# VIVA_PIC16_1591A.net
KiCad netlist of a schematic drawn in EAGLE
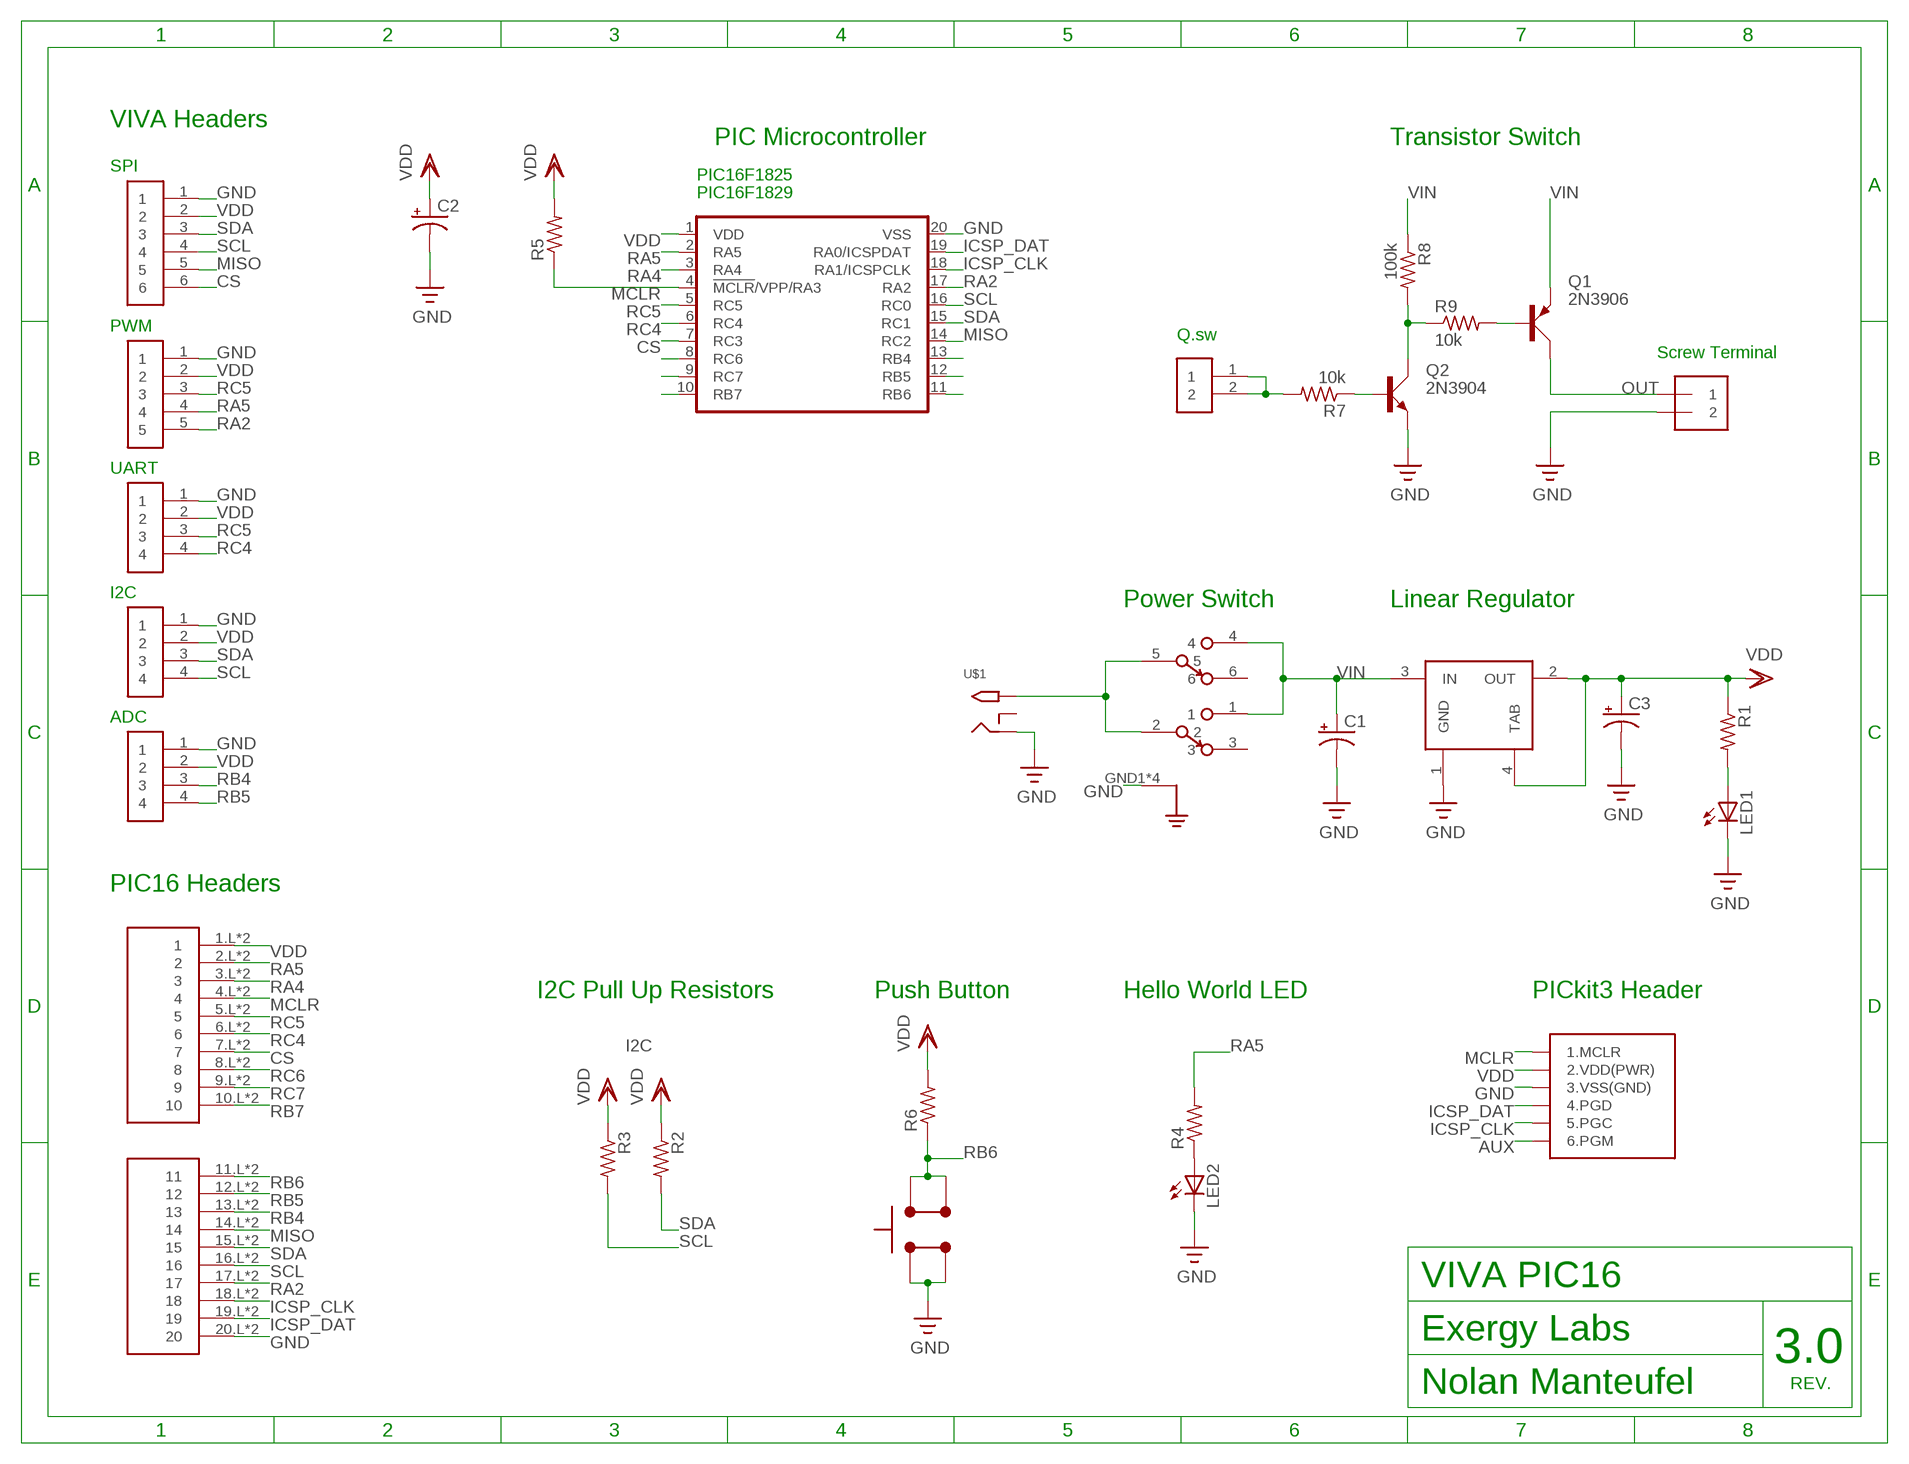
[diagram p0: schematic, sheet 1]

(export (version "E")
  (design (tool "Eeschema 10.0.6"))
  (components
    (comp (ref "C1")
      (value "CPOL-USE2.5-6")
      (footprint "eagle-import:E2,5-6")
      (libsource (lib "eagle-import") (part "CPOL-USE2.5-6"))
    )
    (comp (ref "C2")
      (value "CPOL-USE2.5-6")
      (footprint "eagle-import:E2,5-6")
      (libsource (lib "eagle-import") (part "CPOL-USE2.5-6"))
    )
    (comp (ref "C3")
      (value "CPOL-USE2.5-6")
      (footprint "eagle-import:E2,5-6")
      (libsource (lib "eagle-import") (part "CPOL-USE2.5-6"))
    )
    (comp (ref "J1")
      (value "1X2-3.5MM")
      (footprint "eagle-import:1X2-3.5MM")
      (libsource (lib "eagle-import") (part "1X2-3.5MM"))
    )
    (comp (ref "LED1")
      (value "LED5MM")
      (footprint "eagle-import:LED5MM")
      (libsource (lib "eagle-import") (part "LED5MM"))
    )
    (comp (ref "LED2")
      (value "LED5MM")
      (footprint "eagle-import:LED5MM")
      (libsource (lib "eagle-import") (part "LED5MM"))
    )
    (comp (ref "PIC16F1823")
      (value "PIC16F1829")
      (footprint "eagle-import:DIL20")
      (libsource (lib "eagle-import") (part "PIC16F1829"))
    )
    (comp (ref "Q1")
      (value "2N3906")
      (footprint "eagle-import:TO92-EBC-OVAL")
      (libsource (lib "eagle-import") (part "2N3906TO92-EBC-OVAL"))
    )
    (comp (ref "Q2")
      (value "2N3904")
      (footprint "eagle-import:TO92-EBC-OVAL")
      (libsource (lib "eagle-import") (part "2N3904TO92-EBC-OVAL"))
    )
    (comp (ref "R1")
      (value "R-US_0204/5")
      (footprint "eagle-import:0204_5")
      (libsource (lib "eagle-import") (part "R-US_0204/5"))
    )
    (comp (ref "R2")
      (value "R-US_0204/5")
      (footprint "eagle-import:0204_5")
      (libsource (lib "eagle-import") (part "R-US_0204/5"))
    )
    (comp (ref "R3")
      (value "R-US_0204/5")
      (footprint "eagle-import:0204_5")
      (libsource (lib "eagle-import") (part "R-US_0204/5"))
    )
    (comp (ref "R4")
      (value "R-US_0204/5")
      (footprint "eagle-import:0204_5")
      (libsource (lib "eagle-import") (part "R-US_0204/5"))
    )
    (comp (ref "R5")
      (value "R-US_0204/5")
      (footprint "eagle-import:0204_5")
      (libsource (lib "eagle-import") (part "R-US_0204/5"))
    )
    (comp (ref "R6")
      (value "R-US_0204/5")
      (footprint "eagle-import:0204_5")
      (libsource (lib "eagle-import") (part "R-US_0204/5"))
    )
    (comp (ref "R7")
      (value "10k")
      (footprint "eagle-import:0204_5")
      (libsource (lib "eagle-import") (part "R-US_0204/5"))
    )
    (comp (ref "R8")
      (value "100k")
      (footprint "eagle-import:0204_5")
      (libsource (lib "eagle-import") (part "R-US_0204/5"))
    )
    (comp (ref "R9")
      (value "10k")
      (footprint "eagle-import:0204_5")
      (libsource (lib "eagle-import") (part "R-US_0204/5"))
    )
    (comp (ref "U$1")
      (value "2.1MMJACKTHM")
      (footprint "eagle-import:PJ-102A")
      (libsource (lib "eagle-import") (part "2.1MMJACKTHM"))
    )
    (comp (ref "U$3")
      (value "SWITCH_OS202013")
      (footprint "eagle-import:OS202013MT5QN1")
      (libsource (lib "eagle-import") (part "SWITCH_OS202013"))
    )
    (comp (ref "U$4")
      (value "PUSHBUTTON_THD")
      (footprint "eagle-import:PUSHBUTTON_1301_9303")
      (libsource (lib "eagle-import") (part "PUSHBUTTON_THD"))
    )
    (comp (ref "U$5")
      (value "PINS_5")
      (footprint "eagle-import:PINS_5")
      (libsource (lib "eagle-import") (part "PINS_5"))
    )
    (comp (ref "U$6")
      (value "PINS_4")
      (footprint "eagle-import:PINS_4")
      (libsource (lib "eagle-import") (part "PINS_4"))
    )
    (comp (ref "U$7")
      (value "PINS_4")
      (footprint "eagle-import:PINS_4")
      (libsource (lib "eagle-import") (part "PINS_4"))
    )
    (comp (ref "U$8")
      (value "PINS_4")
      (footprint "eagle-import:PINS_4")
      (libsource (lib "eagle-import") (part "PINS_4"))
    )
    (comp (ref "U$9")
      (value "PINS_6")
      (footprint "eagle-import:PINS_6")
      (libsource (lib "eagle-import") (part "PINS_6"))
    )
    (comp (ref "U$10")
      (value "PINS_2")
      (footprint "eagle-import:PINS_2")
      (libsource (lib "eagle-import") (part "PINS_2"))
    )
    (comp (ref "U$11")
      (value "PICKIT3")
      (footprint "eagle-import:PICKIT3")
      (libsource (lib "eagle-import") (part "PICKIT3"))
    )
    (comp (ref "U$12")
      (value "VIVA_PIC16")
      (footprint "eagle-import:VIVA_PIC16")
      (libsource (lib "eagle-import") (part "VIVA_PIC16"))
    )
    (comp (ref "U1")
      (value "REGULATOR_SCHSOT223")
      (footprint "eagle-import:SOT223")
      (libsource (lib "eagle-import") (part "REGULATOR_SCHSOT223"))
    )
  )
  (nets
    (net (code "1") (name "/AUX") (class "Default")
      (node (ref "U$11") (pin "6") (pinfunction "6.PGM_6") (pintype "bidirectional"))
    )
    (net (code "2") (name "/CS") (class "Default")
      (node (ref "PIC16F1823") (pin "7") (pinfunction "RC3_7") (pintype "bidirectional"))
      (node (ref "U$12") (pin "7.L") (pinfunction "7_7.L") (pintype "bidirectional"))
      (node (ref "U$12") (pin "7.R") (pinfunction "7_7.R") (pintype "bidirectional"))
      (node (ref "U$9") (pin "6") (pinfunction "6_6") (pintype "bidirectional"))
    )
    (net (code "3") (name "/ICSP_CLK") (class "Default")
      (node (ref "PIC16F1823") (pin "18") (pinfunction "RA1/ICSPCLK_18") (pintype "bidirectional"))
      (node (ref "U$11") (pin "5") (pinfunction "5.PGC_5") (pintype "bidirectional"))
      (node (ref "U$12") (pin "18.L") (pinfunction "18_18.L") (pintype "bidirectional"))
      (node (ref "U$12") (pin "18.R") (pinfunction "18_18.R") (pintype "bidirectional"))
    )
    (net (code "4") (name "/ICSP_DAT") (class "Default")
      (node (ref "PIC16F1823") (pin "19") (pinfunction "RA0/ICSPDAT_19") (pintype "bidirectional"))
      (node (ref "U$11") (pin "4") (pinfunction "4.PGD_4") (pintype "bidirectional"))
      (node (ref "U$12") (pin "19.L") (pinfunction "19_19.L") (pintype "bidirectional"))
      (node (ref "U$12") (pin "19.R") (pinfunction "19_19.R") (pintype "bidirectional"))
    )
    (net (code "5") (name "/MCLR") (class "Default")
      (node (ref "PIC16F1823") (pin "4") (pinfunction "~{MCLR}/VPP/RA3_4") (pintype "bidirectional"))
      (node (ref "R5") (pin "1") (pinfunction "1_1") (pintype "passive"))
      (node (ref "U$11") (pin "1") (pinfunction "1.MCLR_1") (pintype "bidirectional"))
      (node (ref "U$12") (pin "4.L") (pinfunction "4_4.L") (pintype "bidirectional"))
      (node (ref "U$12") (pin "4.R") (pinfunction "4_4.R") (pintype "bidirectional"))
    )
    (net (code "6") (name "/MISO") (class "Default")
      (node (ref "PIC16F1823") (pin "14") (pinfunction "RC2_14") (pintype "bidirectional"))
      (node (ref "U$12") (pin "14.L") (pinfunction "14_14.L") (pintype "bidirectional"))
      (node (ref "U$12") (pin "14.R") (pinfunction "14_14.R") (pintype "bidirectional"))
      (node (ref "U$9") (pin "5") (pinfunction "5_5") (pintype "bidirectional"))
    )
    (net (code "7") (name "/OUT") (class "Default")
      (node (ref "J1") (pin "1") (pinfunction "1_1") (pintype "passive"))
      (node (ref "Q1") (pin "C") (pinfunction "C_C") (pintype "passive"))
    )
    (net (code "8") (name "/RA2") (class "Default")
      (node (ref "PIC16F1823") (pin "17") (pinfunction "RA2_17") (pintype "bidirectional"))
      (node (ref "U$12") (pin "17.L") (pinfunction "17_17.L") (pintype "bidirectional"))
      (node (ref "U$12") (pin "17.R") (pinfunction "17_17.R") (pintype "bidirectional"))
      (node (ref "U$5") (pin "5") (pinfunction "5_5") (pintype "bidirectional"))
    )
    (net (code "9") (name "/RA4") (class "Default")
      (node (ref "PIC16F1823") (pin "3") (pinfunction "RA4_3") (pintype "bidirectional"))
      (node (ref "U$12") (pin "3.L") (pinfunction "3_3.L") (pintype "bidirectional"))
      (node (ref "U$12") (pin "3.R") (pinfunction "3_3.R") (pintype "bidirectional"))
    )
    (net (code "10") (name "/RA5") (class "Default")
      (node (ref "PIC16F1823") (pin "2") (pinfunction "RA5_2") (pintype "bidirectional"))
      (node (ref "R4") (pin "2") (pinfunction "2_2") (pintype "passive"))
      (node (ref "U$12") (pin "2.L") (pinfunction "2_2.L") (pintype "bidirectional"))
      (node (ref "U$12") (pin "2.R") (pinfunction "2_2.R") (pintype "bidirectional"))
      (node (ref "U$5") (pin "4") (pinfunction "4_4") (pintype "bidirectional"))
    )
    (net (code "11") (name "/RB4") (class "Default")
      (node (ref "PIC16F1823") (pin "13") (pinfunction "RB4_13") (pintype "bidirectional"))
      (node (ref "U$12") (pin "13.L") (pinfunction "13_13.L") (pintype "bidirectional"))
      (node (ref "U$12") (pin "13.R") (pinfunction "13_13.R") (pintype "bidirectional"))
      (node (ref "U$8") (pin "3") (pinfunction "3_3") (pintype "bidirectional"))
    )
    (net (code "12") (name "/RB5") (class "Default")
      (node (ref "PIC16F1823") (pin "12") (pinfunction "RB5_12") (pintype "bidirectional"))
      (node (ref "U$12") (pin "12.L") (pinfunction "12_12.L") (pintype "bidirectional"))
      (node (ref "U$12") (pin "12.R") (pinfunction "12_12.R") (pintype "bidirectional"))
      (node (ref "U$8") (pin "4") (pinfunction "4_4") (pintype "bidirectional"))
    )
    (net (code "13") (name "/RB6") (class "Default")
      (node (ref "PIC16F1823") (pin "11") (pinfunction "RB6_11") (pintype "bidirectional"))
      (node (ref "R6") (pin "1") (pinfunction "1_1") (pintype "passive"))
      (node (ref "U$12") (pin "11.L") (pinfunction "11_11.L") (pintype "bidirectional"))
      (node (ref "U$12") (pin "11.R") (pinfunction "11_11.R") (pintype "bidirectional"))
      (node (ref "U$4") (pin "3") (pinfunction "3_3") (pintype "bidirectional"))
      (node (ref "U$4") (pin "4") (pinfunction "4_4") (pintype "bidirectional"))
    )
    (net (code "14") (name "/RB7") (class "Default")
      (node (ref "PIC16F1823") (pin "10") (pinfunction "RB7_10") (pintype "bidirectional"))
      (node (ref "U$12") (pin "10.L") (pinfunction "10_10.L") (pintype "bidirectional"))
      (node (ref "U$12") (pin "10.R") (pinfunction "10_10.R") (pintype "bidirectional"))
    )
    (net (code "15") (name "/RC4") (class "Default")
      (node (ref "PIC16F1823") (pin "6") (pinfunction "RC4_6") (pintype "bidirectional"))
      (node (ref "U$12") (pin "6.L") (pinfunction "6_6.L") (pintype "bidirectional"))
      (node (ref "U$12") (pin "6.R") (pinfunction "6_6.R") (pintype "bidirectional"))
      (node (ref "U$6") (pin "4") (pinfunction "4_4") (pintype "bidirectional"))
    )
    (net (code "16") (name "/RC5") (class "Default")
      (node (ref "PIC16F1823") (pin "5") (pinfunction "RC5_5") (pintype "power_in"))
      (node (ref "U$12") (pin "5.L") (pinfunction "5_5.L") (pintype "bidirectional"))
      (node (ref "U$12") (pin "5.R") (pinfunction "5_5.R") (pintype "bidirectional"))
      (node (ref "U$5") (pin "3") (pinfunction "3_3") (pintype "bidirectional"))
      (node (ref "U$6") (pin "3") (pinfunction "3_3") (pintype "bidirectional"))
    )
    (net (code "17") (name "/RC6") (class "Default")
      (node (ref "PIC16F1823") (pin "8") (pinfunction "RC6_8") (pintype "bidirectional"))
      (node (ref "U$12") (pin "8.L") (pinfunction "8_8.L") (pintype "bidirectional"))
      (node (ref "U$12") (pin "8.R") (pinfunction "8_8.R") (pintype "bidirectional"))
    )
    (net (code "18") (name "/RC7") (class "Default")
      (node (ref "PIC16F1823") (pin "9") (pinfunction "RC7_9") (pintype "bidirectional"))
      (node (ref "U$12") (pin "9.L") (pinfunction "9_9.L") (pintype "bidirectional"))
      (node (ref "U$12") (pin "9.R") (pinfunction "9_9.R") (pintype "bidirectional"))
    )
    (net (code "19") (name "/SCL") (class "Default")
      (node (ref "PIC16F1823") (pin "16") (pinfunction "RC0_16") (pintype "power_in"))
      (node (ref "R3") (pin "2") (pinfunction "2_2") (pintype "passive"))
      (node (ref "U$12") (pin "16.L") (pinfunction "16_16.L") (pintype "bidirectional"))
      (node (ref "U$12") (pin "16.R") (pinfunction "16_16.R") (pintype "bidirectional"))
      (node (ref "U$7") (pin "4") (pinfunction "4_4") (pintype "bidirectional"))
      (node (ref "U$9") (pin "4") (pinfunction "4_4") (pintype "bidirectional"))
    )
    (net (code "20") (name "/SDA") (class "Default")
      (node (ref "PIC16F1823") (pin "15") (pinfunction "RC1_15") (pintype "bidirectional"))
      (node (ref "R2") (pin "2") (pinfunction "2_2") (pintype "passive"))
      (node (ref "U$12") (pin "15.L") (pinfunction "15_15.L") (pintype "bidirectional"))
      (node (ref "U$12") (pin "15.R") (pinfunction "15_15.R") (pintype "bidirectional"))
      (node (ref "U$7") (pin "3") (pinfunction "3_3") (pintype "bidirectional"))
      (node (ref "U$9") (pin "3") (pinfunction "3_3") (pintype "bidirectional"))
    )
    (net (code "21") (name "/VIN") (class "Default")
      (node (ref "C1") (pin "+") (pinfunction "+_+") (pintype "passive"))
      (node (ref "Q1") (pin "E") (pinfunction "E_E") (pintype "passive"))
      (node (ref "R8") (pin "1") (pinfunction "1_1") (pintype "passive"))
      (node (ref "U$3") (pin "1") (pinfunction "1_1") (pintype "bidirectional"))
      (node (ref "U$3") (pin "4") (pinfunction "4_4") (pintype "bidirectional"))
      (node (ref "U1") (pin "3") (pinfunction "IN_3") (pintype "bidirectional"))
    )
    (net (code "22") (name "GND") (class "Default")
      (node (ref "C1") (pin "-") (pinfunction "-_-") (pintype "passive"))
      (node (ref "C2") (pin "-") (pinfunction "-_-") (pintype "passive"))
      (node (ref "C3") (pin "-") (pinfunction "-_-") (pintype "passive"))
      (node (ref "J1") (pin "2") (pinfunction "2_2") (pintype "passive"))
      (node (ref "LED1") (pin "K") (pinfunction "C_K") (pintype "passive"))
      (node (ref "LED2") (pin "K") (pinfunction "C_K") (pintype "passive"))
      (node (ref "PIC16F1823") (pin "20") (pinfunction "VSS_20") (pintype "bidirectional"))
      (node (ref "Q2") (pin "E") (pinfunction "E_E") (pintype "passive"))
      (node (ref "U$1") (pin "RING") (pinfunction "RING_RING") (pintype "bidirectional"))
      (node (ref "U$11") (pin "3") (pinfunction "3.VSS(GND)_3") (pintype "bidirectional"))
      (node (ref "U$12") (pin "20.L") (pinfunction "20_20.L") (pintype "bidirectional"))
      (node (ref "U$12") (pin "20.R") (pinfunction "20_20.R") (pintype "bidirectional"))
      (node (ref "U$3") (pin "GND1") (pinfunction "GND_GND1") (pintype "bidirectional"))
      (node (ref "U$3") (pin "GND2") (pinfunction "GND_GND2") (pintype "bidirectional"))
      (node (ref "U$3") (pin "GND3") (pinfunction "GND_GND3") (pintype "bidirectional"))
      (node (ref "U$3") (pin "GND4") (pinfunction "GND_GND4") (pintype "bidirectional"))
      (node (ref "U$4") (pin "1") (pinfunction "1_1") (pintype "bidirectional"))
      (node (ref "U$4") (pin "2") (pinfunction "2_2") (pintype "bidirectional"))
      (node (ref "U$5") (pin "1") (pinfunction "1_1") (pintype "bidirectional"))
      (node (ref "U$6") (pin "1") (pinfunction "1_1") (pintype "bidirectional"))
      (node (ref "U$7") (pin "1") (pinfunction "1_1") (pintype "bidirectional"))
      (node (ref "U$8") (pin "1") (pinfunction "1_1") (pintype "bidirectional"))
      (node (ref "U$9") (pin "1") (pinfunction "1_1") (pintype "bidirectional"))
      (node (ref "U1") (pin "1") (pinfunction "GND_1") (pintype "bidirectional"))
    )
    (net (code "23") (name "Net-(LED1-PadA)") (class "Default")
      (node (ref "LED1") (pin "A") (pinfunction "A_A") (pintype "passive"))
      (node (ref "R1") (pin "2") (pinfunction "2_2") (pintype "passive"))
    )
    (net (code "24") (name "Net-(LED2-PadA)") (class "Default")
      (node (ref "LED2") (pin "A") (pinfunction "A_A") (pintype "passive"))
      (node (ref "R4") (pin "1") (pinfunction "1_1") (pintype "passive"))
    )
    (net (code "25") (name "Net-(Q1-PadB)") (class "Default")
      (node (ref "Q1") (pin "B") (pinfunction "B_B") (pintype "passive"))
      (node (ref "R9") (pin "2") (pinfunction "2_2") (pintype "passive"))
    )
    (net (code "26") (name "Net-(Q2-PadB)") (class "Default")
      (node (ref "Q2") (pin "B") (pinfunction "B_B") (pintype "passive"))
      (node (ref "R7") (pin "1") (pinfunction "1_1") (pintype "passive"))
    )
    (net (code "27") (name "Net-(Q2-PadC)") (class "Default")
      (node (ref "Q2") (pin "C") (pinfunction "C_C") (pintype "passive"))
      (node (ref "R8") (pin "2") (pinfunction "2_2") (pintype "passive"))
      (node (ref "R9") (pin "1") (pinfunction "1_1") (pintype "passive"))
    )
    (net (code "28") (name "Net-(R7-Pad2)") (class "Default")
      (node (ref "R7") (pin "2") (pinfunction "2_2") (pintype "passive"))
      (node (ref "U$10") (pin "1") (pinfunction "1_1") (pintype "bidirectional"))
      (node (ref "U$10") (pin "2") (pinfunction "2_2") (pintype "bidirectional"))
    )
    (net (code "29") (name "Net-(U$1-PadTIP)") (class "Default")
      (node (ref "U$1") (pin "TIP") (pinfunction "TIP_TIP") (pintype "bidirectional"))
      (node (ref "U$3") (pin "2") (pinfunction "2_2") (pintype "bidirectional"))
      (node (ref "U$3") (pin "5") (pinfunction "5_5") (pintype "bidirectional"))
    )
    (net (code "30") (name "VDD") (class "Default")
      (node (ref "C2") (pin "+") (pinfunction "+_+") (pintype "passive"))
      (node (ref "C3") (pin "+") (pinfunction "+_+") (pintype "passive"))
      (node (ref "PIC16F1823") (pin "1") (pinfunction "VDD_1") (pintype "bidirectional"))
      (node (ref "R1") (pin "1") (pinfunction "1_1") (pintype "passive"))
      (node (ref "R2") (pin "1") (pinfunction "1_1") (pintype "passive"))
      (node (ref "R3") (pin "1") (pinfunction "1_1") (pintype "passive"))
      (node (ref "R5") (pin "2") (pinfunction "2_2") (pintype "passive"))
      (node (ref "R6") (pin "2") (pinfunction "2_2") (pintype "passive"))
      (node (ref "U$11") (pin "2") (pinfunction "2.VDD(PWR)_2") (pintype "bidirectional"))
      (node (ref "U$12") (pin "1.L") (pinfunction "1_1.L") (pintype "bidirectional"))
      (node (ref "U$12") (pin "1.R") (pinfunction "1_1.R") (pintype "bidirectional"))
      (node (ref "U$5") (pin "2") (pinfunction "2_2") (pintype "bidirectional"))
      (node (ref "U$6") (pin "2") (pinfunction "2_2") (pintype "bidirectional"))
      (node (ref "U$7") (pin "2") (pinfunction "2_2") (pintype "bidirectional"))
      (node (ref "U$8") (pin "2") (pinfunction "2_2") (pintype "bidirectional"))
      (node (ref "U$9") (pin "2") (pinfunction "2_2") (pintype "bidirectional"))
      (node (ref "U1") (pin "2") (pinfunction "OUT_2") (pintype "bidirectional"))
      (node (ref "U1") (pin "4") (pinfunction "TAB_4") (pintype "bidirectional"))
    )
    (net (code "31") (name "unconnected-(U$1-PadRING_SW)") (class "Default")
      (node (ref "U$1") (pin "RING_SW") (pinfunction "RING_SW_RING_SW") (pintype "bidirectional"))
    )
    (net (code "32") (name "unconnected-(U$3-Pad3)") (class "Default")
      (node (ref "U$3") (pin "3") (pinfunction "3_3") (pintype "bidirectional"))
    )
    (net (code "33") (name "unconnected-(U$3-Pad6)") (class "Default")
      (node (ref "U$3") (pin "6") (pinfunction "6_6") (pintype "bidirectional"))
    )
  )
)
